# snowman.net
KiCad netlist of a schematic drawn in EAGLE
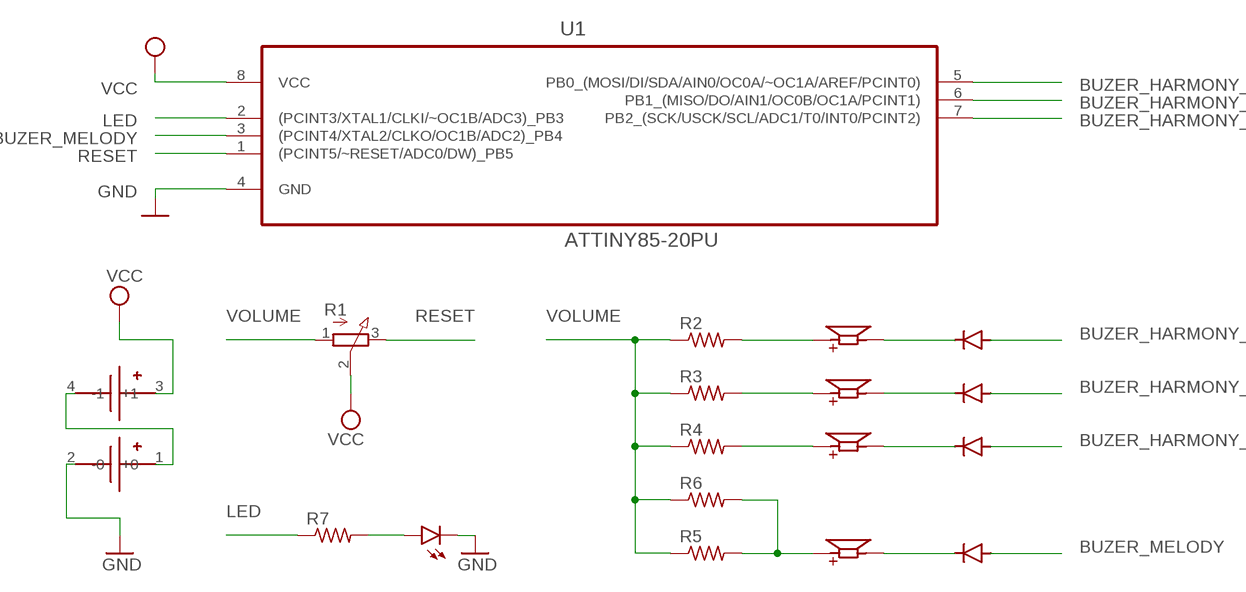
[diagram p0: schematic, sheet 1]

(export (version "E")
  (design (tool "Eeschema 10.0.6"))
  (components
    (comp (ref "D1")
      (value "GF1")
      (footprint "eagle-import:SMA-DO214AC")
      (libsource (lib "eagle-import") (part "GF1"))
    )
    (comp (ref "D2")
      (value "GF1")
      (footprint "eagle-import:SMA-DO214AC")
      (libsource (lib "eagle-import") (part "GF1"))
    )
    (comp (ref "D3")
      (value "GF1")
      (footprint "eagle-import:SMA-DO214AC")
      (libsource (lib "eagle-import") (part "GF1"))
    )
    (comp (ref "D4")
      (value "GF1")
      (footprint "eagle-import:SMA-DO214AC")
      (libsource (lib "eagle-import") (part "GF1"))
    )
    (comp (ref "LED1")
      (value "LED3MM")
      (footprint "eagle-import:LED3MM")
      (libsource (lib "eagle-import") (part "LED3MM"))
    )
    (comp (ref "LS1")
      (value "CMT-8530S-SMT")
      (footprint "eagle-import:CUI_CMT-8530S-SMT")
      (fields (field (name "MF") "CUI Devices") (field (name "MP") "CMT-8530S-SMT-TR"))
      (libsource (lib "eagle-import") (part "CMT-8530S-SMT"))
    )
    (comp (ref "LS2")
      (value "CMT-8530S-SMT")
      (footprint "eagle-import:CUI_CMT-8530S-SMT")
      (fields (field (name "MF") "CUI Devices") (field (name "MP") "CMT-8530S-SMT-TR"))
      (libsource (lib "eagle-import") (part "CMT-8530S-SMT"))
    )
    (comp (ref "LS3")
      (value "CMT-8530S-SMT")
      (footprint "eagle-import:CUI_CMT-8530S-SMT")
      (fields (field (name "MF") "CUI Devices") (field (name "MP") "CMT-8530S-SMT-TR"))
      (libsource (lib "eagle-import") (part "CMT-8530S-SMT"))
    )
    (comp (ref "LS4")
      (value "CMT-8530S-SMT")
      (footprint "eagle-import:CUI_CMT-8530S-SMT")
      (fields (field (name "MF") "CUI Devices") (field (name "MP") "CMT-8530S-SMT-TR"))
      (libsource (lib "eagle-import") (part "CMT-8530S-SMT"))
    )
    (comp (ref "R1")
      (value "3RP/1610N")
      (footprint "eagle-import:3RP_1610N")
      (libsource (lib "eagle-import") (part "3RP/1610N"))
    )
    (comp (ref "R2")
      (value "R-US_R0805")
      (footprint "eagle-import:R0805")
      (libsource (lib "eagle-import") (part "R-US_R0805"))
    )
    (comp (ref "R3")
      (value "R-US_R0805")
      (footprint "eagle-import:R0805")
      (libsource (lib "eagle-import") (part "R-US_R0805"))
    )
    (comp (ref "R4")
      (value "R-US_R0805")
      (footprint "eagle-import:R0805")
      (libsource (lib "eagle-import") (part "R-US_R0805"))
    )
    (comp (ref "R5")
      (value "R-US_R0805")
      (footprint "eagle-import:R0805")
      (libsource (lib "eagle-import") (part "R-US_R0805"))
    )
    (comp (ref "R6")
      (value "R-US_R0805")
      (footprint "eagle-import:R0805")
      (libsource (lib "eagle-import") (part "R-US_R0805"))
    )
    (comp (ref "R7")
      (value "R-US_R0805")
      (footprint "eagle-import:R0805")
      (libsource (lib "eagle-import") (part "R-US_R0805"))
    )
    (comp (ref "U$1")
      (value "BLOSSOM-BLM-18650-2PCS")
      (footprint "eagle-import:BLOSSOM-BLM-18650-2PCS")
      (libsource (lib "eagle-import") (part "BLOSSOM-BLM-18650-2PCS"))
    )
    (comp (ref "U1")
      (value "ATTINY85-20PU")
      (footprint "eagle-import:DIP254P762X533-8")
      (fields (field (name "MF") "Microchip"))
      (libsource (lib "eagle-import") (part "ATTINY85-20PU"))
    )
  )
  (nets
    (net (code "1") (name "/BUZER_HARMONY_1") (class "Default")
      (node (ref "D4") (pin "A") (pinfunction "A_A") (pintype "passive"))
      (node (ref "U1") (pin "7") (pinfunction "PB2_(SCK/USCK/SCL/ADC1/T0/INT0/PCINT2)_7") (pintype "bidirectional"))
    )
    (net (code "2") (name "/BUZER_HARMONY_2") (class "Default")
      (node (ref "D3") (pin "A") (pinfunction "A_A") (pintype "passive"))
      (node (ref "U1") (pin "6") (pinfunction "PB1_(MISO/DO/AIN1/OC0B/OC1A/PCINT1)_6") (pintype "bidirectional"))
    )
    (net (code "3") (name "/BUZER_HARMONY_3") (class "Default")
      (node (ref "D2") (pin "A") (pinfunction "A_A") (pintype "passive"))
      (node (ref "U1") (pin "5") (pinfunction "PB0_(MOSI/DI/SDA/AIN0/OC0A/~{OC1A/AREF/PCINT0})_5") (pintype "bidirectional"))
    )
    (net (code "4") (name "/BUZER_MELODY") (class "Default")
      (node (ref "D1") (pin "A") (pinfunction "A_A") (pintype "passive"))
      (node (ref "U1") (pin "3") (pinfunction "(PCINT4/XTAL2/CLKO/OC1B/ADC2)_PB4_3") (pintype "bidirectional"))
    )
    (net (code "5") (name "/LED") (class "Default")
      (node (ref "R7") (pin "1") (pinfunction "1_1") (pintype "passive"))
      (node (ref "U1") (pin "2") (pinfunction "(PCINT3/XTAL1/CLKI/~{OC1B/ADC3})_PB3_2") (pintype "bidirectional"))
    )
    (net (code "6") (name "/RESET") (class "Default")
      (node (ref "R1") (pin "3") (pinfunction "E_3") (pintype "passive"))
      (node (ref "U1") (pin "1") (pinfunction "(PCINT5/~{RESET/ADC0/DW})_PB5_1") (pintype "bidirectional"))
    )
    (net (code "7") (name "/VOLUME") (class "Default")
      (node (ref "R1") (pin "1") (pinfunction "A_1") (pintype "passive"))
      (node (ref "R2") (pin "1") (pinfunction "1_1") (pintype "passive"))
      (node (ref "R3") (pin "1") (pinfunction "1_1") (pintype "passive"))
      (node (ref "R4") (pin "1") (pinfunction "1_1") (pintype "passive"))
      (node (ref "R5") (pin "1") (pinfunction "1_1") (pintype "passive"))
      (node (ref "R6") (pin "1") (pinfunction "1_1") (pintype "passive"))
    )
    (net (code "8") (name "GND") (class "Default")
      (node (ref "LED1") (pin "K") (pinfunction "C_K") (pintype "passive"))
      (node (ref "U$1") (pin "2") (pinfunction "-0_2") (pintype "bidirectional"))
      (node (ref "U1") (pin "4") (pinfunction "GND_4") (pintype "passive"))
    )
    (net (code "9") (name "Net-(D1-C)") (class "Default")
      (node (ref "D1") (pin "K") (pinfunction "C_K") (pintype "passive"))
      (node (ref "LS1") (pin "N") (pinfunction "N_N") (pintype "passive"))
    )
    (net (code "10") (name "Net-(D2-C)") (class "Default")
      (node (ref "D2") (pin "K") (pinfunction "C_K") (pintype "passive"))
      (node (ref "LS3") (pin "N") (pinfunction "N_N") (pintype "passive"))
    )
    (net (code "11") (name "Net-(D3-C)") (class "Default")
      (node (ref "D3") (pin "K") (pinfunction "C_K") (pintype "passive"))
      (node (ref "LS4") (pin "N") (pinfunction "N_N") (pintype "passive"))
    )
    (net (code "12") (name "Net-(D4-C)") (class "Default")
      (node (ref "D4") (pin "K") (pinfunction "C_K") (pintype "passive"))
      (node (ref "LS2") (pin "N") (pinfunction "N_N") (pintype "passive"))
    )
    (net (code "13") (name "Net-(LED1-PadA)") (class "Default")
      (node (ref "LED1") (pin "A") (pinfunction "A_A") (pintype "passive"))
      (node (ref "R7") (pin "2") (pinfunction "2_2") (pintype "passive"))
    )
    (net (code "14") (name "Net-(LS1-PadP)") (class "Default")
      (node (ref "LS1") (pin "P") (pinfunction "P_P") (pintype "passive"))
      (node (ref "R5") (pin "2") (pinfunction "2_2") (pintype "passive"))
      (node (ref "R6") (pin "2") (pinfunction "2_2") (pintype "passive"))
    )
    (net (code "15") (name "Net-(LS2-PadP)") (class "Default")
      (node (ref "LS2") (pin "P") (pinfunction "P_P") (pintype "passive"))
      (node (ref "R2") (pin "2") (pinfunction "2_2") (pintype "passive"))
    )
    (net (code "16") (name "Net-(LS3-PadP)") (class "Default")
      (node (ref "LS3") (pin "P") (pinfunction "P_P") (pintype "passive"))
      (node (ref "R4") (pin "2") (pinfunction "2_2") (pintype "passive"))
    )
    (net (code "17") (name "Net-(LS4-PadP)") (class "Default")
      (node (ref "LS4") (pin "P") (pinfunction "P_P") (pintype "passive"))
      (node (ref "R3") (pin "2") (pinfunction "2_2") (pintype "passive"))
    )
    (net (code "18") (name "Net-(U$1-+0)") (class "Default")
      (node (ref "U$1") (pin "1") (pinfunction "+0_1") (pintype "bidirectional"))
      (node (ref "U$1") (pin "4") (pinfunction "-1_4") (pintype "bidirectional"))
    )
    (net (code "19") (name "VCC") (class "Default")
      (node (ref "R1") (pin "2") (pinfunction "S_2") (pintype "passive"))
      (node (ref "U$1") (pin "3") (pinfunction "+1_3") (pintype "bidirectional"))
      (node (ref "U1") (pin "8") (pinfunction "VCC_8") (pintype "power_in"))
    )
  )
)
